# FPGA_ADC4.net
KiCad netlist of a schematic drawn in Altium Designer
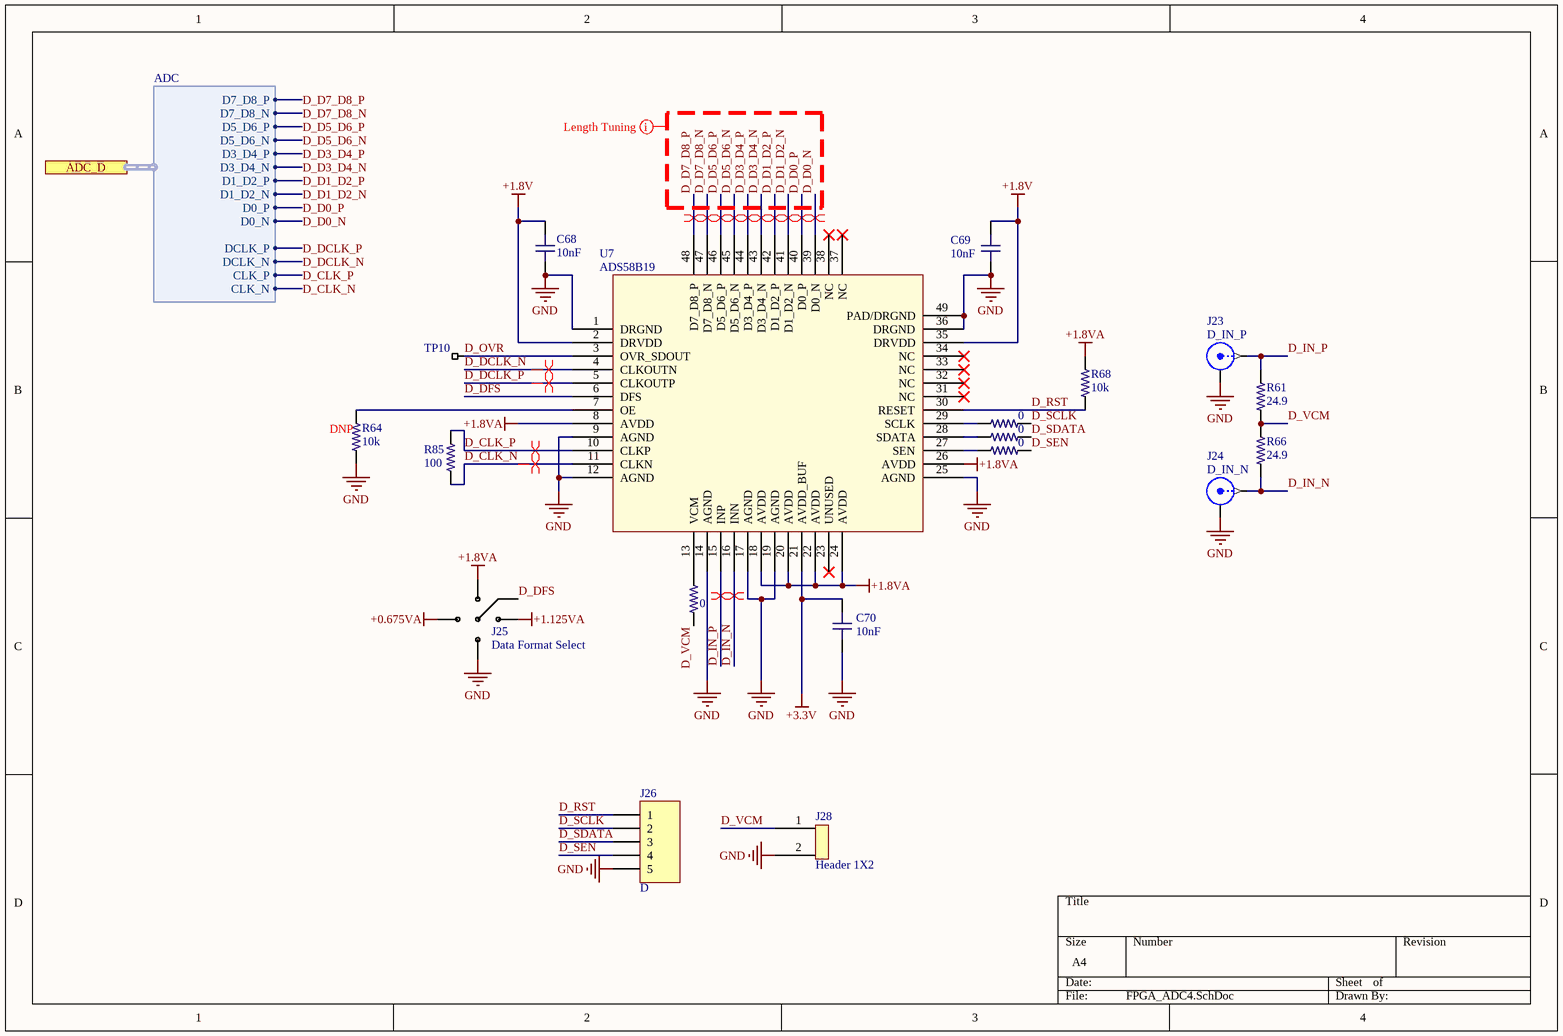
[diagram p0: FPGA_ADC4.SchDoc]

(export (version "E")
  (design (tool "Eeschema 10.0.6"))
  (components
    (comp (ref "C68")
      (value "10nF")
      (footprint "C0603-HIGH-DENSITY")
      (description "CAP CER 10000PF 50V X7R 0603")
      (fields (field (name "Comment") "C0603 10nF 50V X7R"))
      (libsource (lib "Capacitors") (part "C0603 10nF 50V X7R"))
    )
    (comp (ref "C69")
      (value "10nF")
      (footprint "C0603-HIGH-DENSITY")
      (description "CAP CER 10000PF 50V X7R 0603")
      (fields (field (name "Comment") "C0603 10nF 50V X7R"))
      (libsource (lib "Capacitors") (part "C0603 10nF 50V X7R"))
    )
    (comp (ref "C70")
      (value "10nF")
      (footprint "C0603-HIGH-DENSITY")
      (description "CAP CER 10000PF 50V X7R 0603")
      (fields (field (name "Comment") "C0603 10nF 50V X7R"))
      (libsource (lib "Capacitors") (part "C0603 10nF 50V X7R"))
    )
    (comp (ref "J23")
      (value "D_IN_P")
      (footprint "SMA Edge Launch (Horizontal)")
      (description "SMA Connector")
      (libsource (lib "Connectors") (part "SMA"))
    )
    (comp (ref "J24")
      (value "D_IN_N")
      (footprint "SMA Edge Launch (Horizontal)")
      (description "SMA Connector")
      (libsource (lib "Connectors") (part "SMA"))
    )
    (comp (ref "J25")
      (value "Data Format Select")
      (footprint "4P Jumper")
      (description "0603 4 Way Solder Jumper")
      (libsource (lib "Switches") (part "4P Jumper"))
    )
    (comp (ref "J26")
      (value "D")
      (footprint "HDR1X5")
      (description "Header, 5-Pin")
      (fields (field (name "PUBLISHER") "Altium Limited"))
      (libsource (lib "Miscellaneous Connectors") (part "Header 5"))
    )
    (comp (ref "J28")
      (value "Header 1X2")
      (footprint "Header 1x2 TH Pitch 2.54mm")
      (libsource (lib "Connectors") (part "Header 1X2"))
    )
    (comp (ref "R61")
      (value "24.9")
      (footprint "R0603-HIGH-DENSITY")
      (description "Chip Resistor, 0603, 24.9 ohms, 0.1W")
      (fields (field (name "Comment") "RC0603FR-0724R9L"))
      (libsource (lib "Resistors") (part "R0603 24.9R 1%"))
    )
    (comp (ref "R62")
      (value "0")
      (footprint "R0603-IPC")
      (description "RES SMD 0 OHM JUMPER 1/10W 0603")
      (fields (field (name "Comment") "R0603 0"))
      (libsource (lib "Resistors") (part "R0603 0"))
    )
    (comp (ref "R63")
      (value "0")
      (footprint "R0603-IPC")
      (description "RES SMD 0 OHM JUMPER 1/10W 0603")
      (fields (field (name "Comment") "R0603 0"))
      (libsource (lib "Resistors") (part "R0603 0"))
    )
    (comp (ref "R64")
      (value "10k")
      (footprint "R0603-IPC-10K")
      (description "RES SMD 10K OHM 1% 1/10W 0603")
      (fields (field (name "Comment") "R0603 10K 1%"))
      (libsource (lib "Resistors") (part "R0603 10K 1%"))
    )
    (comp (ref "R65")
      (value "0")
      (footprint "R0603-IPC")
      (description "RES SMD 0 OHM JUMPER 1/10W 0603")
      (fields (field (name "Comment") "R0603 0"))
      (libsource (lib "Resistors") (part "R0603 0"))
    )
    (comp (ref "R66")
      (value "24.9")
      (footprint "R0603-HIGH-DENSITY")
      (description "Chip Resistor, 0603, 24.9 ohms, 0.1W")
      (fields (field (name "Comment") "RC0603FR-0724R9L"))
      (libsource (lib "Resistors") (part "R0603 24.9R 1%"))
    )
    (comp (ref "R67")
      (value "0")
      (footprint "R0603-IPC")
      (description "RES SMD 0 OHM JUMPER 1/10W 0603")
      (fields (field (name "Comment") "R0603 0"))
      (libsource (lib "Resistors") (part "R0603 0"))
    )
    (comp (ref "R68")
      (value "10k")
      (footprint "R0603-IPC-10K")
      (description "RES SMD 10K OHM 1% 1/10W 0603")
      (fields (field (name "Comment") "R0603 10K 1%"))
      (libsource (lib "Resistors") (part "R0603 10K 1%"))
    )
    (comp (ref "R85")
      (value "100")
      (footprint "R0402-HIGH-DENSITY")
      (description "Chip Resistor, 0402, 100 ohms, 1%, 1/16 W")
      (fields (field (name "Comment") "R0402 100R 1%"))
      (libsource (lib "Resistors") (part "R0402 100R 1%"))
    )
    (comp (ref "TP10")
      (value "Testpoint_SMT")
      (footprint "TESTPOINT_SMT")
      (description "SMT Test Point")
      (libsource (lib "Virtual Parts") (part "Testpoint_SMT"))
    )
    (comp (ref "U7")
      (value "ADS58B19")
      (footprint "VQFN48")
      (description "Single ADC Pipelined 250Msps 9-bit Parallel/LVDS 48-Pin VQFN")
      (libsource (lib "Integrated Circuits") (part "ADS58B19"))
    )
  )
  (nets
    (net (code "2") (name "+0.675VA") (class "Default")
      (node (ref "J25") (pin "4") (pinfunction "4_4") (pintype "passive"))
    )
    (net (code "3") (name "+1.8V") (class "Default")
      (node (ref "C68") (pin "1") (pintype "passive"))
      (node (ref "C69") (pin "1") (pintype "passive"))
      (node (ref "U7") (pin "2") (pinfunction "DRVDD_2") (pintype "passive"))
      (node (ref "U7") (pin "35") (pinfunction "DRVDD_35") (pintype "passive"))
    )
    (net (code "4") (name "+1.8VA") (class "Default")
      (node (ref "J25") (pin "1") (pinfunction "1_1") (pintype "passive"))
      (node (ref "R68") (pin "2") (pintype "passive"))
      (node (ref "U7") (pin "18") (pinfunction "AVDD_18") (pintype "passive"))
      (node (ref "U7") (pin "20") (pinfunction "AVDD_20") (pintype "passive"))
      (node (ref "U7") (pin "22") (pinfunction "AVDD_22") (pintype "passive"))
      (node (ref "U7") (pin "24") (pinfunction "AVDD_24") (pintype "passive"))
      (node (ref "U7") (pin "26") (pinfunction "AVDD_26") (pintype "passive"))
      (node (ref "U7") (pin "8") (pinfunction "AVDD_8") (pintype "passive"))
    )
    (net (code "5") (name "+1.125VA") (class "Default")
      (node (ref "J25") (pin "2") (pinfunction "2_2") (pintype "passive"))
    )
    (net (code "6") (name "+3.3V") (class "Default")
      (node (ref "C70") (pin "1") (pintype "passive"))
      (node (ref "U7") (pin "21") (pinfunction "AVDD_BUF_21") (pintype "passive"))
    )
    (net (code "7") (name "/D_CLK_N") (class "Default")
      (node (ref "R85") (pin "1") (pintype "passive"))
      (node (ref "U7") (pin "11") (pinfunction "CLKN_11") (pintype "passive"))
    )
    (net (code "8") (name "/D_CLK_P") (class "Default")
      (node (ref "R85") (pin "2") (pintype "passive"))
      (node (ref "U7") (pin "10") (pinfunction "CLKP_10") (pintype "passive"))
    )
    (net (code "9") (name "/D_D0_N") (class "Default")
      (node (ref "U7") (pin "39") (pinfunction "D0_N_39") (pintype "passive"))
    )
    (net (code "10") (name "/D_D0_P") (class "Default")
      (node (ref "U7") (pin "40") (pinfunction "D0_P_40") (pintype "passive"))
    )
    (net (code "11") (name "/D_D1_D2_N") (class "Default")
      (node (ref "U7") (pin "41") (pinfunction "D1_D2_N_41") (pintype "passive"))
    )
    (net (code "12") (name "/D_D1_D2_P") (class "Default")
      (node (ref "U7") (pin "42") (pinfunction "D1_D2_P_42") (pintype "passive"))
    )
    (net (code "13") (name "/D_D3_D4_N") (class "Default")
      (node (ref "U7") (pin "43") (pinfunction "D3_D4_N_43") (pintype "passive"))
    )
    (net (code "14") (name "/D_D3_D4_P") (class "Default")
      (node (ref "U7") (pin "44") (pinfunction "D3_D4_P_44") (pintype "passive"))
    )
    (net (code "15") (name "/D_D5_D6_N") (class "Default")
      (node (ref "U7") (pin "45") (pinfunction "D5_D6_N_45") (pintype "passive"))
    )
    (net (code "16") (name "/D_D5_D6_P") (class "Default")
      (node (ref "U7") (pin "46") (pinfunction "D5_D6_P_46") (pintype "passive"))
    )
    (net (code "17") (name "/D_D7_D8_N") (class "Default")
      (node (ref "U7") (pin "47") (pinfunction "D7_D8_N_47") (pintype "passive"))
    )
    (net (code "18") (name "/D_D7_D8_P") (class "Default")
      (node (ref "U7") (pin "48") (pinfunction "D7_D8_P_48") (pintype "passive"))
    )
    (net (code "19") (name "/D_DCLK_N") (class "Default")
      (node (ref "U7") (pin "4") (pinfunction "CLKOUTN_4") (pintype "passive"))
    )
    (net (code "20") (name "/D_DCLK_P") (class "Default")
      (node (ref "U7") (pin "5") (pinfunction "CLKOUTP_5") (pintype "passive"))
    )
    (net (code "21") (name "/D_DFS") (class "Default")
      (node (ref "J25") (pin "5") (pinfunction "5_5") (pintype "passive"))
      (node (ref "U7") (pin "6") (pinfunction "DFS_6") (pintype "passive"))
    )
    (net (code "22") (name "/D_IN_N") (class "Default")
      (node (ref "J24") (pin "1") (pinfunction "X_1") (pintype "output"))
      (node (ref "R66") (pin "1") (pintype "passive"))
      (node (ref "U7") (pin "16") (pinfunction "INN_16") (pintype "passive"))
    )
    (net (code "23") (name "/D_IN_P") (class "Default")
      (node (ref "J23") (pin "1") (pinfunction "X_1") (pintype "output"))
      (node (ref "R61") (pin "2") (pintype "passive"))
      (node (ref "U7") (pin "15") (pinfunction "INP_15") (pintype "passive"))
    )
    (net (code "24") (name "/D_OVR") (class "Default")
      (node (ref "TP10") (pin "1") (pinfunction "1_1") (pintype "passive"))
      (node (ref "U7") (pin "3") (pinfunction "OVR_SDOUT_3") (pintype "passive"))
    )
    (net (code "25") (name "/D_RST") (class "Default")
      (node (ref "J26") (pin "1") (pinfunction "1_1") (pintype "passive"))
      (node (ref "R68") (pin "1") (pintype "passive"))
      (node (ref "U7") (pin "30") (pinfunction "RESET_30") (pintype "passive"))
    )
    (net (code "26") (name "/D_SCLK") (class "Default")
      (node (ref "J26") (pin "2") (pinfunction "2_2") (pintype "passive"))
      (node (ref "R62") (pin "2") (pintype "passive"))
    )
    (net (code "27") (name "/D_SDATA") (class "Default")
      (node (ref "J26") (pin "3") (pinfunction "3_3") (pintype "passive"))
      (node (ref "R63") (pin "2") (pintype "passive"))
    )
    (net (code "28") (name "/D_SEN") (class "Default")
      (node (ref "J26") (pin "4") (pinfunction "4_4") (pintype "passive"))
      (node (ref "R65") (pin "2") (pintype "passive"))
    )
    (net (code "29") (name "/D_VCM") (class "Default")
      (node (ref "J28") (pin "1") (pintype "passive"))
      (node (ref "R61") (pin "1") (pintype "passive"))
      (node (ref "R66") (pin "2") (pintype "passive"))
      (node (ref "R67") (pin "2") (pintype "passive"))
    )
    (net (code "31") (name "GND") (class "Default")
      (node (ref "C68") (pin "2") (pintype "passive"))
      (node (ref "C69") (pin "2") (pintype "passive"))
      (node (ref "C70") (pin "2") (pintype "passive"))
      (node (ref "J23") (pin "2") (pinfunction "Y_2") (pintype "power_in"))
      (node (ref "J24") (pin "2") (pinfunction "Y_2") (pintype "power_in"))
      (node (ref "J25") (pin "3") (pinfunction "3_3") (pintype "passive"))
      (node (ref "J26") (pin "5") (pinfunction "5_5") (pintype "passive"))
      (node (ref "J28") (pin "2") (pintype "passive"))
      (node (ref "R64") (pin "1") (pintype "passive"))
      (node (ref "U7") (pin "1") (pinfunction "DRGND_1") (pintype "passive"))
      (node (ref "U7") (pin "12") (pinfunction "AGND_12") (pintype "passive"))
      (node (ref "U7") (pin "14") (pinfunction "AGND_14") (pintype "passive"))
      (node (ref "U7") (pin "17") (pinfunction "AGND_17") (pintype "passive"))
      (node (ref "U7") (pin "19") (pinfunction "AGND_19") (pintype "passive"))
      (node (ref "U7") (pin "25") (pinfunction "AGND_25") (pintype "passive"))
      (node (ref "U7") (pin "36") (pinfunction "DRGND_36") (pintype "passive"))
      (node (ref "U7") (pin "49") (pinfunction "PAD/DRGND_49") (pintype "passive"))
      (node (ref "U7") (pin "9") (pinfunction "AGND_9") (pintype "passive"))
    )
    (net (code "32") (name "Net-(U7-OE)") (class "Default")
      (node (ref "R64") (pin "2") (pintype "passive"))
      (node (ref "U7") (pin "7") (pinfunction "OE_7") (pintype "passive"))
    )
    (net (code "33") (name "Net-(U7-SCLK)") (class "Default")
      (node (ref "R62") (pin "1") (pintype "passive"))
      (node (ref "U7") (pin "29") (pinfunction "SCLK_29") (pintype "passive"))
    )
    (net (code "34") (name "Net-(U7-SDATA)") (class "Default")
      (node (ref "R63") (pin "1") (pintype "passive"))
      (node (ref "U7") (pin "28") (pinfunction "SDATA_28") (pintype "passive"))
    )
    (net (code "35") (name "Net-(U7-SEN)") (class "Default")
      (node (ref "R65") (pin "1") (pintype "passive"))
      (node (ref "U7") (pin "27") (pinfunction "SEN_27") (pintype "passive"))
    )
    (net (code "36") (name "Net-(U7-VCM)") (class "Default")
      (node (ref "R67") (pin "1") (pintype "passive"))
      (node (ref "U7") (pin "13") (pinfunction "VCM_13") (pintype "passive"))
    )
    (net (code "37") (name "unconnected-(U7-NC-Pad31)") (class "Default")
      (node (ref "U7") (pin "31") (pinfunction "NC_31") (pintype "passive+no_connect"))
    )
    (net (code "38") (name "unconnected-(U7-NC-Pad32)") (class "Default")
      (node (ref "U7") (pin "32") (pinfunction "NC_32") (pintype "passive+no_connect"))
    )
    (net (code "39") (name "unconnected-(U7-NC-Pad33)") (class "Default")
      (node (ref "U7") (pin "33") (pinfunction "NC_33") (pintype "passive+no_connect"))
    )
    (net (code "40") (name "unconnected-(U7-NC-Pad34)") (class "Default")
      (node (ref "U7") (pin "34") (pinfunction "NC_34") (pintype "passive+no_connect"))
    )
    (net (code "41") (name "unconnected-(U7-NC-Pad37)") (class "Default")
      (node (ref "U7") (pin "37") (pinfunction "NC_37") (pintype "passive+no_connect"))
    )
    (net (code "42") (name "unconnected-(U7-NC-Pad38)") (class "Default")
      (node (ref "U7") (pin "38") (pinfunction "NC_38") (pintype "passive+no_connect"))
    )
    (net (code "43") (name "unconnected-(U7-UNUSED-Pad23)") (class "Default")
      (node (ref "U7") (pin "23") (pinfunction "UNUSED_23") (pintype "passive+no_connect"))
    )
  )
)
